# mini-v1_15-070.net
KiCad netlist of a schematic drawn in EAGLE
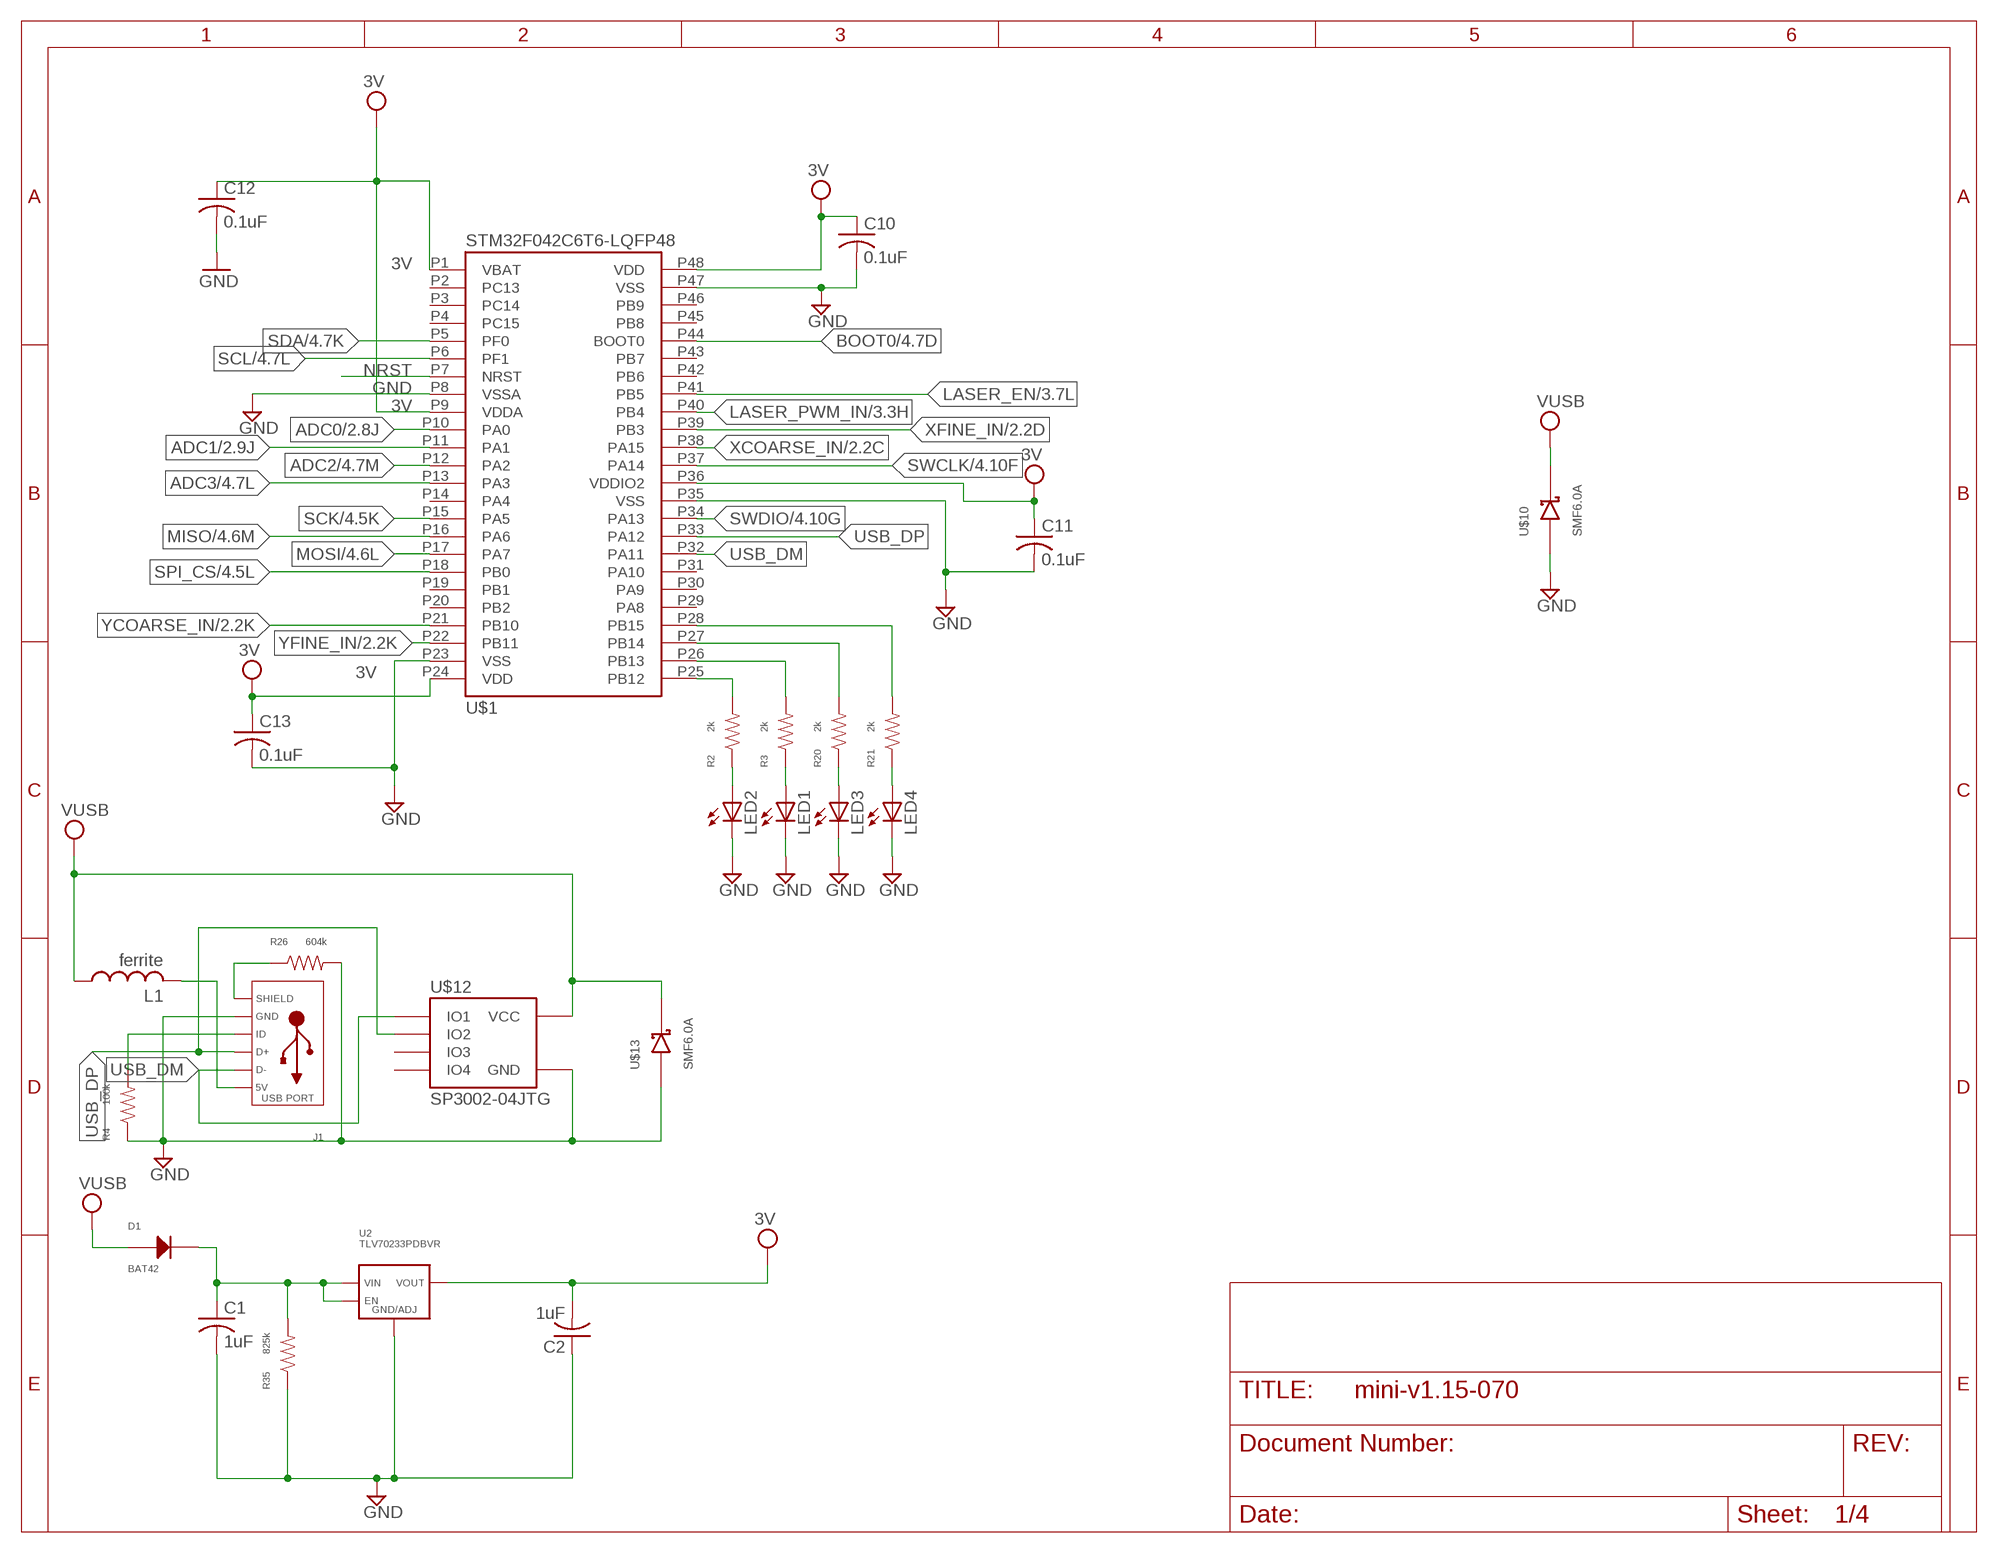
[diagram p0: schematic, sheet 1]
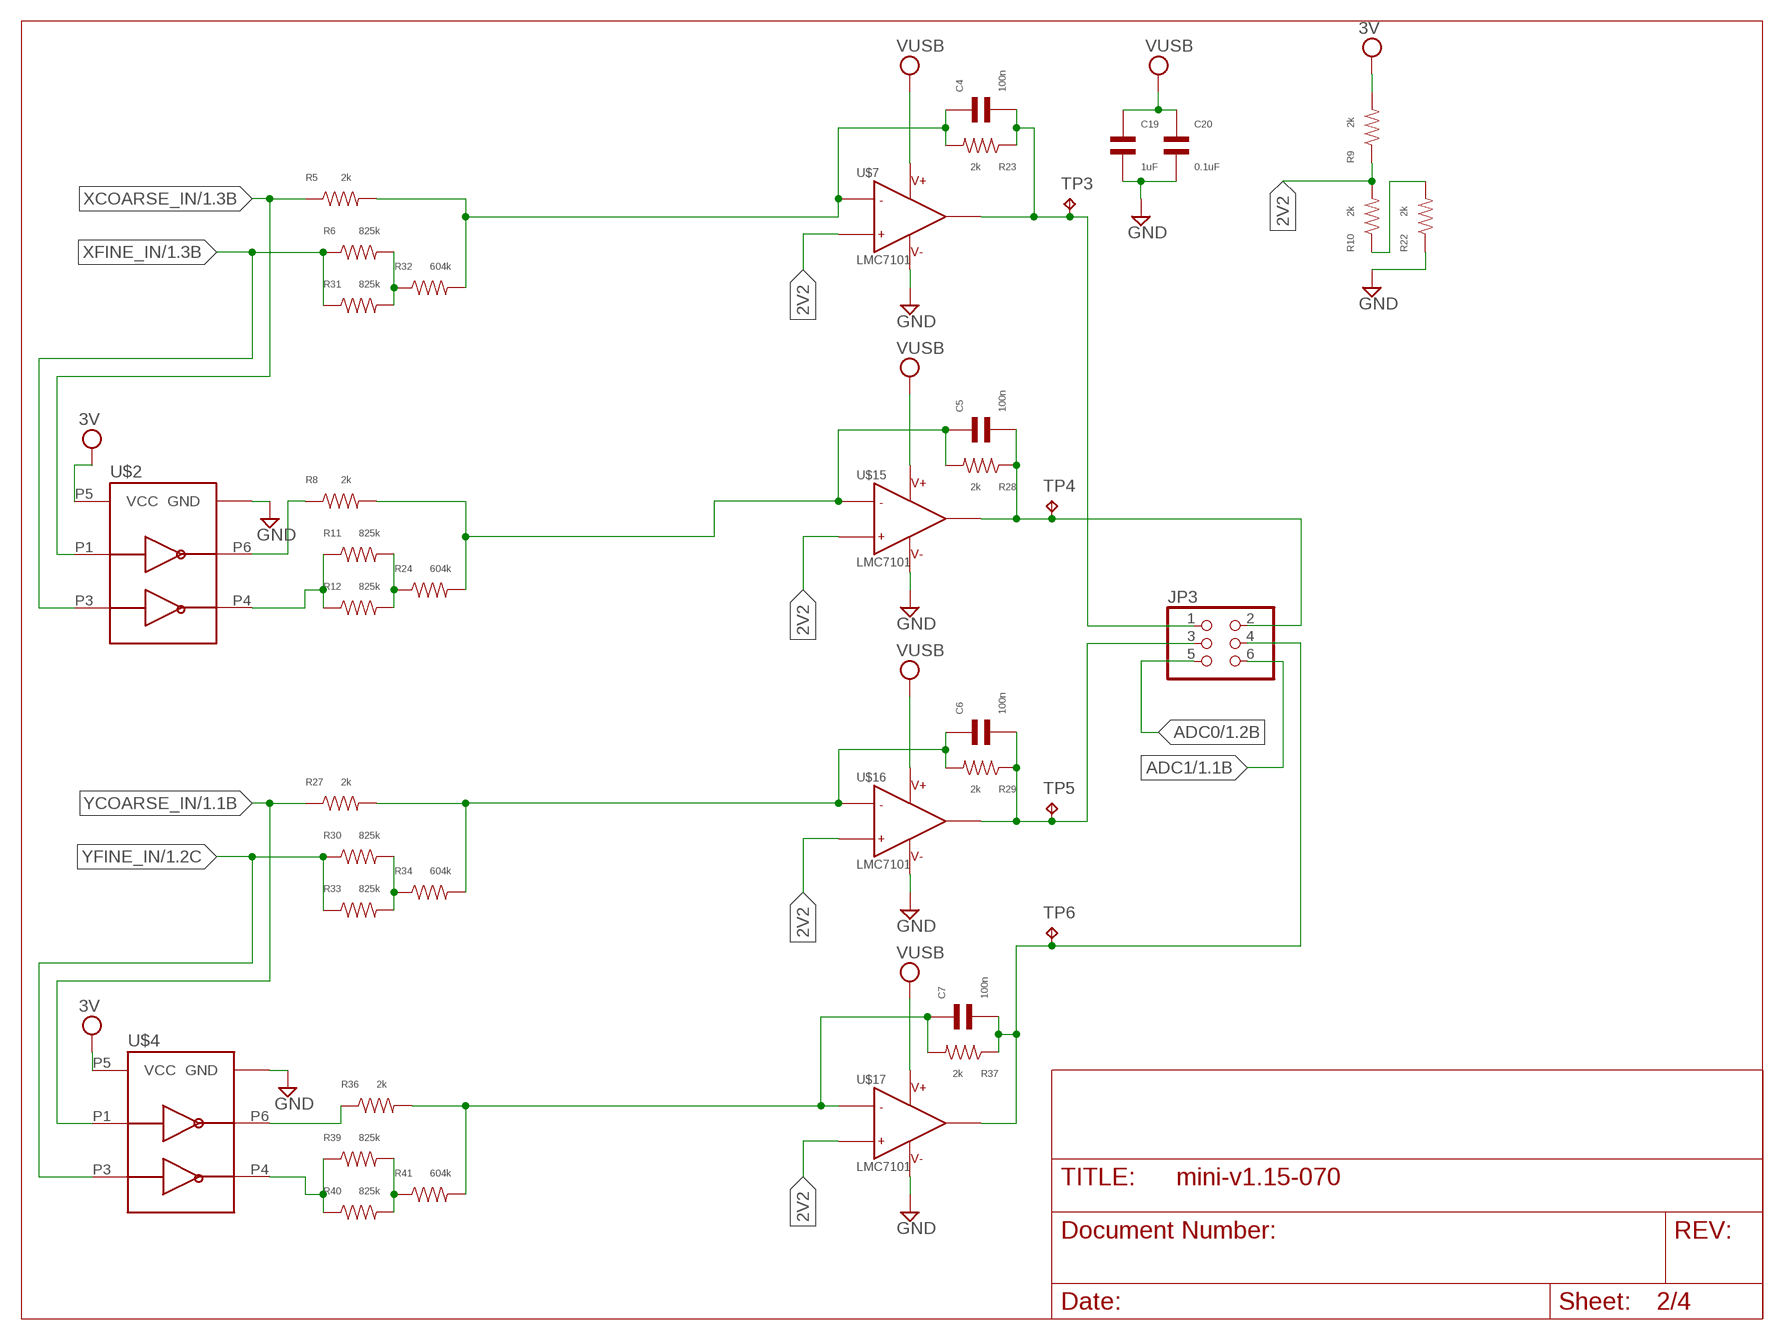
[diagram p1: schematic, sheet 2]
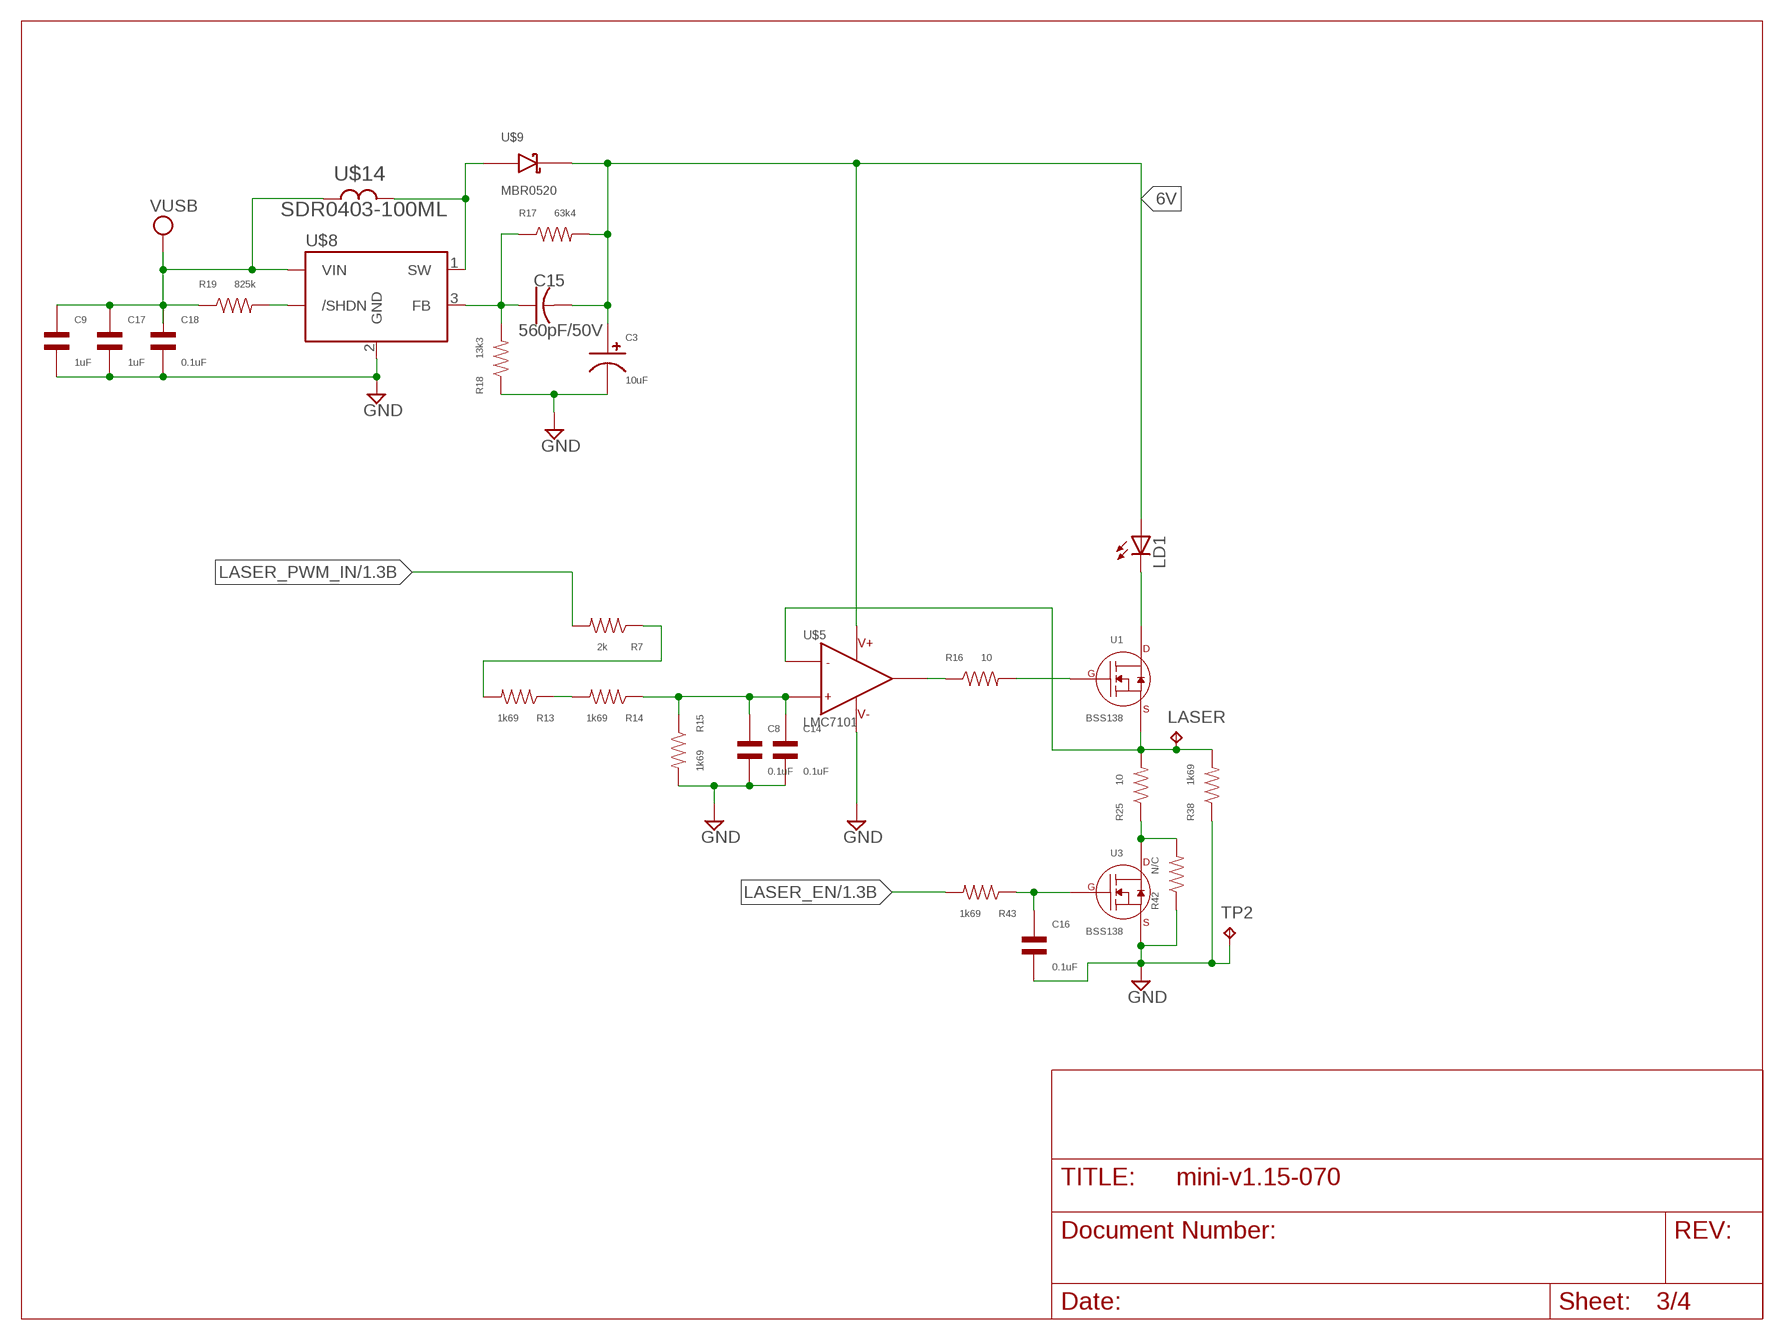
[diagram p2: schematic, sheet 3]
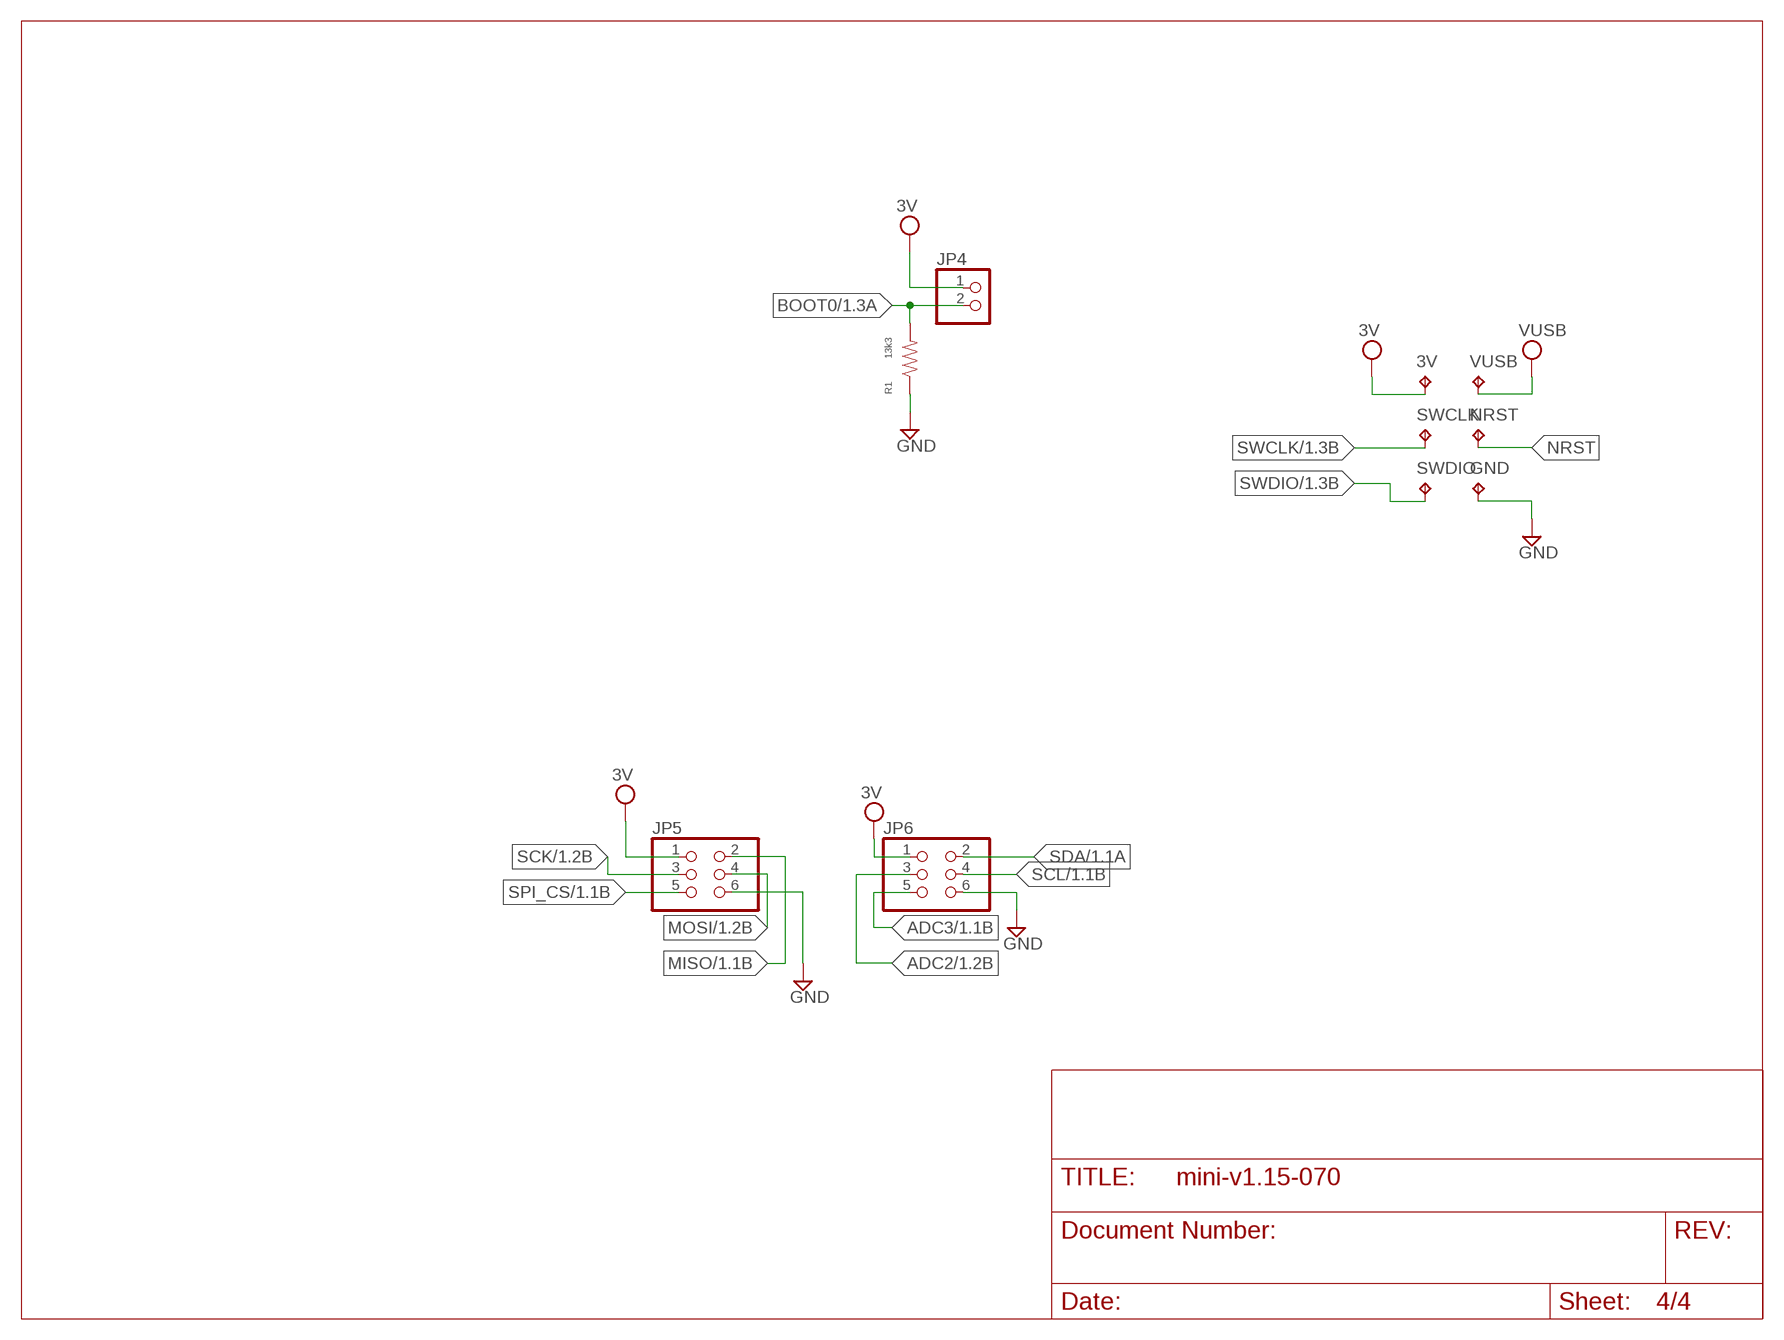
[diagram p3: schematic, sheet 4]

(export (version "E")
  (design (tool "Eeschema 10.0.6"))
  (components
    (comp (ref "C3")
      (value "10uF")
      (footprint "eagle-import:CP4MM")
      (libsource (lib "eagle-import") (part "CAPACITOR_P_4MM"))
    )
    (comp (ref "C8")
      (value "0.1uF")
      (footprint "eagle-import:C0603")
      (libsource (lib "eagle-import") (part "CAPACITOR_NP_0603"))
    )
    (comp (ref "C9")
      (value "1uF")
      (footprint "eagle-import:C0603")
      (libsource (lib "eagle-import") (part "CAPACITOR_NP_0603"))
    )
    (comp (ref "C14")
      (value "0.1uF")
      (footprint "eagle-import:C0603")
      (libsource (lib "eagle-import") (part "CAPACITOR_NP_0603"))
    )
    (comp (ref "C15")
      (value "560pF/50V")
      (footprint "eagle-import:C0603")
      (libsource (lib "eagle-import") (part "C-USC0603"))
    )
    (comp (ref "C16")
      (value "0.1uF")
      (footprint "eagle-import:C0603")
      (libsource (lib "eagle-import") (part "CAPACITOR_NP_0603"))
    )
    (comp (ref "C17")
      (value "1uF")
      (footprint "eagle-import:C0603")
      (libsource (lib "eagle-import") (part "CAPACITOR_NP_0603"))
    )
    (comp (ref "C18")
      (value "0.1uF")
      (footprint "eagle-import:C0603")
      (libsource (lib "eagle-import") (part "CAPACITOR_NP_0603"))
    )
    (comp (ref "LASER")
      (value "TPB2,54")
      (footprint "eagle-import:B2,54")
      (libsource (lib "eagle-import") (part "TPB2,54"))
    )
    (comp (ref "LD1")
      (value "SCOTT_LASERDIODELD3")
      (footprint "eagle-import:SCOTT_LASERDIODE3")
      (fields (field (name "MPN") "3 x (0552-2-15-15-11-27-10-0)"))
      (libsource (lib "eagle-import") (part "SCOTT_LASERDIODELD3"))
    )
    (comp (ref "R7")
      (value "2k")
      (footprint "eagle-import:R0603")
      (libsource (lib "eagle-import") (part "RESISTOR_0603"))
    )
    (comp (ref "R13")
      (value "1k69")
      (footprint "eagle-import:R0603")
      (libsource (lib "eagle-import") (part "RESISTOR_0603"))
    )
    (comp (ref "R14")
      (value "1k69")
      (footprint "eagle-import:R0603")
      (libsource (lib "eagle-import") (part "RESISTOR_0603"))
    )
    (comp (ref "R15")
      (value "1k69")
      (footprint "eagle-import:R0603")
      (libsource (lib "eagle-import") (part "RESISTOR_0603"))
    )
    (comp (ref "R16")
      (value "10")
      (footprint "eagle-import:R0603")
      (libsource (lib "eagle-import") (part "RESISTOR_0603"))
    )
    (comp (ref "R17")
      (value "63k4")
      (footprint "eagle-import:R0603")
      (libsource (lib "eagle-import") (part "RESISTOR_0603"))
    )
    (comp (ref "R18")
      (value "13k3")
      (footprint "eagle-import:R0603")
      (libsource (lib "eagle-import") (part "RESISTOR_0603"))
    )
    (comp (ref "R19")
      (value "825k")
      (footprint "eagle-import:R0603")
      (libsource (lib "eagle-import") (part "RESISTOR_0603"))
    )
    (comp (ref "R25")
      (value "10")
      (footprint "eagle-import:R0603")
      (libsource (lib "eagle-import") (part "RESISTOR_0603"))
    )
    (comp (ref "R38")
      (value "1k69")
      (footprint "eagle-import:R0603")
      (libsource (lib "eagle-import") (part "RESISTOR_0603"))
    )
    (comp (ref "R42")
      (value "N/C")
      (footprint "eagle-import:R0603")
      (libsource (lib "eagle-import") (part "RESISTOR_0603"))
    )
    (comp (ref "R43")
      (value "1k69")
      (footprint "eagle-import:R0603")
      (libsource (lib "eagle-import") (part "RESISTOR_0603"))
    )
    (comp (ref "TP2")
      (value "GND")
      (footprint "eagle-import:B2,54")
      (libsource (lib "eagle-import") (part "TPB2,54"))
    )
    (comp (ref "U$5")
      (value "LMC7101")
      (footprint "eagle-import:SOT23-5")
      (libsource (lib "eagle-import") (part "OPAMP-SINGLELMC7101"))
    )
    (comp (ref "U$8")
      (value "LMR62014")
      (footprint "eagle-import:SOT23-5")
      (libsource (lib "eagle-import") (part "LMR62014"))
    )
    (comp (ref "U$9")
      (value "MBR0520")
      (footprint "eagle-import:SOD123")
      (libsource (lib "eagle-import") (part "MBR0520"))
    )
    (comp (ref "U$14")
      (value "SDR0403-100ML")
      (footprint "eagle-import:SDR0403")
      (libsource (lib "eagle-import") (part "SDR0403"))
    )
    (comp (ref "U1")
      (value "BSS138")
      (footprint "eagle-import:SOT-23-3")
      (libsource (lib "eagle-import") (part "N-CHANNEL_FET_SOT-23-3"))
    )
    (comp (ref "U3")
      (value "BSS138")
      (footprint "eagle-import:SOT-23-3")
      (libsource (lib "eagle-import") (part "N-CHANNEL_FET_SOT-23-3"))
    )
    (comp (ref "C4")
      (value "100n")
      (footprint "eagle-import:C0603")
      (libsource (lib "eagle-import") (part "CAPACITOR_NP_0603"))
    )
    (comp (ref "C5")
      (value "100n")
      (footprint "eagle-import:C0603")
      (libsource (lib "eagle-import") (part "CAPACITOR_NP_0603"))
    )
    (comp (ref "C6")
      (value "100n")
      (footprint "eagle-import:C0603")
      (libsource (lib "eagle-import") (part "CAPACITOR_NP_0603"))
    )
    (comp (ref "C7")
      (value "100n")
      (footprint "eagle-import:C0603")
      (libsource (lib "eagle-import") (part "CAPACITOR_NP_0603"))
    )
    (comp (ref "C19")
      (value "1uF")
      (footprint "eagle-import:C0603")
      (libsource (lib "eagle-import") (part "CAPACITOR_NP_0603"))
    )
    (comp (ref "C20")
      (value "0.1uF")
      (footprint "eagle-import:C0603")
      (libsource (lib "eagle-import") (part "CAPACITOR_NP_0603"))
    )
    (comp (ref "JP3")
      (value "PINHD-2X3")
      (footprint "eagle-import:2X03")
      (libsource (lib "eagle-import") (part "PINHD-2X3"))
    )
    (comp (ref "R5")
      (value "2k")
      (footprint "eagle-import:R0603")
      (libsource (lib "eagle-import") (part "RESISTOR_0603"))
    )
    (comp (ref "R6")
      (value "825k")
      (footprint "eagle-import:R0603")
      (libsource (lib "eagle-import") (part "RESISTOR_0603"))
    )
    (comp (ref "R8")
      (value "2k")
      (footprint "eagle-import:R0603")
      (libsource (lib "eagle-import") (part "RESISTOR_0603"))
    )
    (comp (ref "R9")
      (value "2k")
      (footprint "eagle-import:R0603")
      (libsource (lib "eagle-import") (part "RESISTOR_0603"))
    )
    (comp (ref "R10")
      (value "2k")
      (footprint "eagle-import:R0603")
      (libsource (lib "eagle-import") (part "RESISTOR_0603"))
    )
    (comp (ref "R11")
      (value "825k")
      (footprint "eagle-import:R0603")
      (libsource (lib "eagle-import") (part "RESISTOR_0603"))
    )
    (comp (ref "R12")
      (value "825k")
      (footprint "eagle-import:R0603")
      (libsource (lib "eagle-import") (part "RESISTOR_0603"))
    )
    (comp (ref "R22")
      (value "2k")
      (footprint "eagle-import:R0603")
      (libsource (lib "eagle-import") (part "RESISTOR_0603"))
    )
    (comp (ref "R23")
      (value "2k")
      (footprint "eagle-import:R0603")
      (libsource (lib "eagle-import") (part "RESISTOR_0603"))
    )
    (comp (ref "R24")
      (value "604k")
      (footprint "eagle-import:R0603")
      (libsource (lib "eagle-import") (part "RESISTOR_0603"))
    )
    (comp (ref "R27")
      (value "2k")
      (footprint "eagle-import:R0603")
      (libsource (lib "eagle-import") (part "RESISTOR_0603"))
    )
    (comp (ref "R28")
      (value "2k")
      (footprint "eagle-import:R0603")
      (libsource (lib "eagle-import") (part "RESISTOR_0603"))
    )
    (comp (ref "R29")
      (value "2k")
      (footprint "eagle-import:R0603")
      (libsource (lib "eagle-import") (part "RESISTOR_0603"))
    )
    (comp (ref "R30")
      (value "825k")
      (footprint "eagle-import:R0603")
      (libsource (lib "eagle-import") (part "RESISTOR_0603"))
    )
    (comp (ref "R31")
      (value "825k")
      (footprint "eagle-import:R0603")
      (libsource (lib "eagle-import") (part "RESISTOR_0603"))
    )
    (comp (ref "R32")
      (value "604k")
      (footprint "eagle-import:R0603")
      (libsource (lib "eagle-import") (part "RESISTOR_0603"))
    )
    (comp (ref "R33")
      (value "825k")
      (footprint "eagle-import:R0603")
      (libsource (lib "eagle-import") (part "RESISTOR_0603"))
    )
    (comp (ref "R34")
      (value "604k")
      (footprint "eagle-import:R0603")
      (libsource (lib "eagle-import") (part "RESISTOR_0603"))
    )
    (comp (ref "R36")
      (value "2k")
      (footprint "eagle-import:R0603")
      (libsource (lib "eagle-import") (part "RESISTOR_0603"))
    )
    (comp (ref "R37")
      (value "2k")
      (footprint "eagle-import:R0603")
      (libsource (lib "eagle-import") (part "RESISTOR_0603"))
    )
    (comp (ref "R39")
      (value "825k")
      (footprint "eagle-import:R0603")
      (libsource (lib "eagle-import") (part "RESISTOR_0603"))
    )
    (comp (ref "R40")
      (value "825k")
      (footprint "eagle-import:R0603")
      (libsource (lib "eagle-import") (part "RESISTOR_0603"))
    )
    (comp (ref "R41")
      (value "604k")
      (footprint "eagle-import:R0603")
      (libsource (lib "eagle-import") (part "RESISTOR_0603"))
    )
    (comp (ref "TP3")
      (value "TPB1,27")
      (footprint "eagle-import:B1,27")
      (libsource (lib "eagle-import") (part "TPB1,27"))
    )
    (comp (ref "TP4")
      (value "TPB1,27")
      (footprint "eagle-import:B1,27")
      (libsource (lib "eagle-import") (part "TPB1,27"))
    )
    (comp (ref "TP5")
      (value "TPB1,27")
      (footprint "eagle-import:B1,27")
      (libsource (lib "eagle-import") (part "TPB1,27"))
    )
    (comp (ref "TP6")
      (value "TPB1,27")
      (footprint "eagle-import:B1,27")
      (libsource (lib "eagle-import") (part "TPB1,27"))
    )
    (comp (ref "U$2")
      (value "NC7WZ14P6X")
      (footprint "eagle-import:SC70-6")
      (libsource (lib "eagle-import") (part "NC7WZ14P6X"))
    )
    (comp (ref "U$4")
      (value "NC7WZ14P6X")
      (footprint "eagle-import:SC70-6")
      (libsource (lib "eagle-import") (part "NC7WZ14P6X"))
    )
    (comp (ref "U$7")
      (value "LMC7101")
      (footprint "eagle-import:SOT23-5")
      (libsource (lib "eagle-import") (part "LMC7101"))
    )
    (comp (ref "U$15")
      (value "LMC7101")
      (footprint "eagle-import:SOT23-5")
      (libsource (lib "eagle-import") (part "LMC7101"))
    )
    (comp (ref "U$16")
      (value "LMC7101")
      (footprint "eagle-import:SOT23-5")
      (libsource (lib "eagle-import") (part "LMC7101"))
    )
    (comp (ref "U$17")
      (value "LMC7101")
      (footprint "eagle-import:SOT23-5")
      (libsource (lib "eagle-import") (part "LMC7101"))
    )
    (comp (ref "3V")
      (value "TPB1,27")
      (footprint "eagle-import:B1,27")
      (libsource (lib "eagle-import") (part "TPB1,27"))
    )
    (comp (ref "GND")
      (value "TPB1,27")
      (footprint "eagle-import:B1,27")
      (libsource (lib "eagle-import") (part "TPB1,27"))
    )
    (comp (ref "JP4")
      (value "PINHD-1X2")
      (footprint "eagle-import:1X02")
      (libsource (lib "eagle-import") (part "PINHD-1X2"))
    )
    (comp (ref "JP5")
      (value "PINHD-2X3")
      (footprint "eagle-import:2X03")
      (libsource (lib "eagle-import") (part "PINHD-2X3"))
    )
    (comp (ref "JP6")
      (value "PINHD-2X3")
      (footprint "eagle-import:2X03")
      (libsource (lib "eagle-import") (part "PINHD-2X3"))
    )
    (comp (ref "NRST")
      (value "TPB1,27")
      (footprint "eagle-import:B1,27")
      (libsource (lib "eagle-import") (part "TPB1,27"))
    )
    (comp (ref "R1")
      (value "13k3")
      (footprint "eagle-import:R0603")
      (libsource (lib "eagle-import") (part "RESISTOR_0603"))
    )
    (comp (ref "SWCLK")
      (value "TPB1,27")
      (footprint "eagle-import:B1,27")
      (libsource (lib "eagle-import") (part "TPB1,27"))
    )
    (comp (ref "SWDIO")
      (value "TPB1,27")
      (footprint "eagle-import:B1,27")
      (libsource (lib "eagle-import") (part "TPB1,27"))
    )
    (comp (ref "VUSB")
      (value "TPB1,27")
      (footprint "eagle-import:B1,27")
      (libsource (lib "eagle-import") (part "TPB1,27"))
    )
    (comp (ref "C1")
      (value "1uF")
      (footprint "eagle-import:C0603")
      (libsource (lib "eagle-import") (part "C-USC0603"))
    )
    (comp (ref "C2")
      (value "1uF")
      (footprint "eagle-import:C0603")
      (libsource (lib "eagle-import") (part "C-USC0603"))
    )
    (comp (ref "C10")
      (value "0.1uF")
      (footprint "eagle-import:C0603")
      (libsource (lib "eagle-import") (part "C-USC0603"))
    )
    (comp (ref "C11")
      (value "0.1uF")
      (footprint "eagle-import:C0603")
      (libsource (lib "eagle-import") (part "C-USC0603"))
    )
    (comp (ref "C12")
      (value "0.1uF")
      (footprint "eagle-import:C0603")
      (libsource (lib "eagle-import") (part "C-USC0603"))
    )
    (comp (ref "C13")
      (value "0.1uF")
      (footprint "eagle-import:C0603")
      (libsource (lib "eagle-import") (part "C-USC0603"))
    )
    (comp (ref "D1")
      (value "BAT42")
      (footprint "eagle-import:SOD-123")
      (libsource (lib "eagle-import") (part "DIODE_SOD-123"))
    )
    (comp (ref "J1")
      (value "USB_MICRO_RIGHT")
      (footprint "eagle-import:MICROUSB-RIGHT")
      (libsource (lib "eagle-import") (part "USB_MICRO_RIGHT"))
    )
    (comp (ref "L1")
      (value "ferrite")
      (footprint "eagle-import:C0603")
      (libsource (lib "eagle-import") (part "L-US"))
    )
    (comp (ref "LED1")
      (value "LEDCHIP-LED0603")
      (footprint "eagle-import:CHIP-LED0603")
      (libsource (lib "eagle-import") (part "LEDCHIP-LED0603"))
    )
    (comp (ref "LED2")
      (value "LEDCHIP-LED0603")
      (footprint "eagle-import:CHIP-LED0603")
      (libsource (lib "eagle-import") (part "LEDCHIP-LED0603"))
    )
    (comp (ref "LED3")
      (value "LEDCHIP-LED0603")
      (footprint "eagle-import:CHIP-LED0603")
      (libsource (lib "eagle-import") (part "LEDCHIP-LED0603"))
    )
    (comp (ref "LED4")
      (value "LEDCHIP-LED0603")
      (footprint "eagle-import:CHIP-LED0603")
      (libsource (lib "eagle-import") (part "LEDCHIP-LED0603"))
    )
    (comp (ref "R2")
      (value "2k")
      (footprint "eagle-import:R0603")
      (libsource (lib "eagle-import") (part "RESISTOR_0603"))
    )
    (comp (ref "R3")
      (value "2k")
      (footprint "eagle-import:R0603")
      (libsource (lib "eagle-import") (part "RESISTOR_0603"))
    )
    (comp (ref "R4")
      (value "100k")
      (footprint "eagle-import:R0603")
      (libsource (lib "eagle-import") (part "RESISTOR_0603"))
    )
    (comp (ref "R20")
      (value "2k")
      (footprint "eagle-import:R0603")
      (libsource (lib "eagle-import") (part "RESISTOR_0603"))
    )
    (comp (ref "R21")
      (value "2k")
      (footprint "eagle-import:R0603")
      (libsource (lib "eagle-import") (part "RESISTOR_0603"))
    )
    (comp (ref "R26")
      (value "604k")
      (footprint "eagle-import:R0603")
      (libsource (lib "eagle-import") (part "RESISTOR_0603"))
    )
    (comp (ref "R35")
      (value "825k")
      (footprint "eagle-import:R0603")
      (libsource (lib "eagle-import") (part "RESISTOR_0603"))
    )
    (comp (ref "U$1")
      (value "STM32F042C6T6-LQFP48")
      (footprint "eagle-import:LQFP48")
      (libsource (lib "eagle-import") (part "STM32F042-LQFP48"))
    )
    (comp (ref "U$10")
      (value "SMF6.0A")
      (footprint "eagle-import:SOD123")
      (libsource (lib "eagle-import") (part "MBR0520"))
    )
    (comp (ref "U$12")
      (value "SP3002-04JTG")
      (footprint "eagle-import:SC70-6")
      (libsource (lib "eagle-import") (part "SP3002"))
    )
    (comp (ref "U$13")
      (value "SMF6.0A")
      (footprint "eagle-import:SOD123")
      (libsource (lib "eagle-import") (part "MBR0520"))
    )
    (comp (ref "U2")
      (value "TLV70233PDBVR")
      (footprint "eagle-import:SOT-23-5")
      (libsource (lib "eagle-import") (part "TLV70233PDBVR"))
    )
  )
  (nets
    (net (code "1") (name "2V2") (class "Default")
      (node (ref "R10") (pin "P$2") (pinfunction "P$2_P$2") (pintype "passive"))
      (node (ref "R9") (pin "P$1") (pinfunction "P$1_P$1") (pintype "passive"))
      (node (ref "U$15") (pin "3") (pinfunction "P3_3") (pintype "bidirectional"))
      (node (ref "U$16") (pin "3") (pinfunction "P3_3") (pintype "bidirectional"))
      (node (ref "U$17") (pin "3") (pinfunction "P3_3") (pintype "bidirectional"))
      (node (ref "U$7") (pin "3") (pinfunction "P3_3") (pintype "bidirectional"))
    )
    (net (code "2") (name "3V") (class "Default")
      (node (ref "3V") (pin "TP") (pinfunction "TP_TP") (pintype "input"))
      (node (ref "C10") (pin "1") (pinfunction "1_1") (pintype "passive"))
      (node (ref "C11") (pin "1") (pinfunction "1_1") (pintype "passive"))
      (node (ref "C12") (pin "1") (pinfunction "1_1") (pintype "passive"))
      (node (ref "C13") (pin "1") (pinfunction "1_1") (pintype "passive"))
      (node (ref "C2") (pin "2") (pinfunction "2_2") (pintype "passive"))
      (node (ref "JP4") (pin "1") (pinfunction "1_1") (pintype "passive"))
      (node (ref "JP5") (pin "1") (pinfunction "1_1") (pintype "passive"))
      (node (ref "JP6") (pin "1") (pinfunction "1_1") (pintype "passive"))
      (node (ref "R9") (pin "P$2") (pinfunction "P$2_P$2") (pintype "passive"))
      (node (ref "U$1") (pin "P1") (pinfunction "VBAT_P1") (pintype "bidirectional"))
      (node (ref "U$1") (pin "P24") (pinfunction "VDD_P24") (pintype "bidirectional"))
      (node (ref "U$1") (pin "P36") (pinfunction "VDDIO2_P36") (pintype "bidirectional"))
      (node (ref "U$1") (pin "P48") (pinfunction "VDD_P48") (pintype "bidirectional"))
      (node (ref "U$1") (pin "P9") (pinfunction "VDDA_P9") (pintype "bidirectional"))
      (node (ref "U$2") (pin "P5") (pinfunction "VCC_P5") (pintype "power_in"))
      (node (ref "U$4") (pin "P5") (pinfunction "VCC_P5") (pintype "power_in"))
      (node (ref "U2") (pin "P$5") (pinfunction "VOUT_P$5") (pintype "bidirectional"))
    )
    (net (code "3") (name "6V") (class "Default")
      (node (ref "C15") (pin "2") (pinfunction "2_2") (pintype "passive"))
      (node (ref "C3") (pin "P$1") (pinfunction "P$1_P$1") (pintype "passive"))
      (node (ref "LD1") (pin "P$1") (pinfunction "A_P$1") (pintype "passive"))
      (node (ref "R17") (pin "P$2") (pinfunction "P$2_P$2") (pintype "passive"))
      (node (ref "U$5") (pin "2") (pinfunction "V+_2") (pintype "power_in"))
      (node (ref "U$9") (pin "CATHODE") (pinfunction "CATHODE_CATHODE") (pintype "bidirectional"))
    )
    (net (code "4") (name "ADC0") (class "Default")
      (node (ref "JP3") (pin "5") (pinfunction "5_5") (pintype "passive"))
      (node (ref "U$1") (pin "P10") (pinfunction "PA0_P10") (pintype "bidirectional"))
    )
    (net (code "5") (name "ADC1") (class "Default")
      (node (ref "JP3") (pin "6") (pinfunction "6_6") (pintype "passive"))
      (node (ref "U$1") (pin "P11") (pinfunction "PA1_P11") (pintype "bidirectional"))
    )
    (net (code "6") (name "ADC2") (class "Default")
      (node (ref "JP6") (pin "3") (pinfunction "3_3") (pintype "passive"))
      (node (ref "U$1") (pin "P12") (pinfunction "PA2_P12") (pintype "bidirectional"))
    )
    (net (code "7") (name "ADC3") (class "Default")
      (node (ref "JP6") (pin "5") (pinfunction "5_5") (pintype "passive"))
      (node (ref "U$1") (pin "P13") (pinfunction "PA3_P13") (pintype "bidirectional"))
    )
    (net (code "8") (name "BOOT0") (class "Default")
      (node (ref "JP4") (pin "2") (pinfunction "2_2") (pintype "passive"))
      (node (ref "R1") (pin "P$2") (pinfunction "P$2_P$2") (pintype "passive"))
      (node (ref "U$1") (pin "P44") (pinfunction "BOOT0_P44") (pintype "bidirectional"))
    )
    (net (code "9") (name "GND") (class "Default")
      (node (ref "C1") (pin "2") (pinfunction "2_2") (pintype "passive"))
      (node (ref "C10") (pin "2") (pinfunction "2_2") (pintype "passive"))
      (node (ref "C11") (pin "2") (pinfunction "2_2") (pintype "passive"))
      (node (ref "C12") (pin "2") (pinfunction "2_2") (pintype "passive"))
      (node (ref "C13") (pin "2") (pinfunction "2_2") (pintype "passive"))
      (node (ref "C14") (pin "P$2") (pinfunction "P$2_P$2") (pintype "passive"))
      (node (ref "C16") (pin "P$2") (pinfunction "P$2_P$2") (pintype "passive"))
      (node (ref "C17") (pin "P$2") (pinfunction "P$2_P$2") (pintype "passive"))
      (node (ref "C18") (pin "P$2") (pinfunction "P$2_P$2") (pintype "passive"))
      (node (ref "C19") (pin "P$2") (pinfunction "P$2_P$2") (pintype "passive"))
      (node (ref "C2") (pin "1") (pinfunction "1_1") (pintype "passive"))
      (node (ref "C20") (pin "P$2") (pinfunction "P$2_P$2") (pintype "passive"))
      (node (ref "C3") (pin "P$2") (pinfunction "P$2_P$2") (pintype "passive"))
      (node (ref "C8") (pin "P$2") (pinfunction "P$2_P$2") (pintype "passive"))
      (node (ref "C9") (pin "P$2") (pinfunction "P$2_P$2") (pintype "passive"))
      (node (ref "GND") (pin "TP") (pinfunction "TP_TP") (pintype "input"))
      (node (ref "J1") (pin "5") (pinfunction "GND_5") (pintype "power_in"))
      (node (ref "JP5") (pin "6") (pinfunction "6_6") (pintype "passive"))
      (node (ref "JP6") (pin "6") (pinfunction "6_6") (pintype "passive"))
      (node (ref "LED1") (pin "C") (pinfunction "C_C") (pintype "passive"))
      (node (ref "LED2") (pin "C") (pinfunction "C_C") (pintype "passive"))
      (node (ref "LED3") (pin "C") (pinfunction "C_C") (pintype "passive"))
      (node (ref "LED4") (pin "C") (pinfunction "C_C") (pintype "passive"))
      (node (ref "R1") (pin "P$1") (pinfunction "P$1_P$1") (pintype "passive"))
      (node (ref "R15") (pin "P$2") (pinfunction "P$2_P$2") (pintype "passive"))
      (node (ref "R18") (pin "P$1") (pinfunction "P$1_P$1") (pintype "passive"))
      (node (ref "R22") (pin "P$1") (pinfunction "P$1_P$1") (pintype "passive"))
      (node (ref "R26") (pin "P$2") (pinfunction "P$2_P$2") (pintype "passive"))
      (node (ref "R35") (pin "P$1") (pinfunction "P$1_P$1") (pintype "passive"))
      (node (ref "R38") (pin "P$1") (pinfunction "P$1_P$1") (pintype "passive"))
      (node (ref "R4") (pin "P$1") (pinfunction "P$1_P$1") (pintype "passive"))
      (node (ref "R42") (pin "P$1") (pinfunction "P$1_P$1") (pintype "passive"))
      (node (ref "TP2") (pin "TP") (pinfunction "TP_TP") (pintype "input"))
      (node (ref "U$1") (pin "P23") (pinfunction "VSS_P23") (pintype "bidirectional"))
      (node (ref "U$1") (pin "P35") (pinfunction "VSS_P35") (pintype "bidirectional"))
      (node (ref "U$1") (pin "P47") (pinfunction "VSS_P47") (pintype "bidirectional"))
      (node (ref "U$1") (pin "P8") (pinfunction "VSSA_P8") (pintype "bidirectional"))
      (node (ref "U$10") (pin "ANODE") (pinfunction "ANODE_ANODE") (pintype "bidirectional"))
      (node (ref "U$12") (pin "P2") (pinfunction "GND_P2") (pintype "power_in"))
      (node (ref "U$13") (pin "ANODE") (pinfunction "ANODE_ANODE") (pintype "bidirectional"))
      (node (ref "U$15") (pin "5") (pinfunction "P5_5") (pintype "power_in"))
      (node (ref "U$16") (pin "5") (pinfunction "P5_5") (pintype "power_in"))
      (node (ref "U$17") (pin "5") (pinfunction "P5_5") (pintype "power_in"))
      (node (ref "U$2") (pin "P2") (pinfunction "GND_P2") (pintype "power_in"))
      (node (ref "U$4") (pin "P2") (pinfunction "GND_P2") (pintype "power_in"))
      (node (ref "U$5") (pin "5") (pinfunction "V-_5") (pintype "power_in"))
      (node (ref "U$7") (pin "5") (pinfunction "P5_5") (pintype "power_in"))
      (node (ref "U$8") (pin "2") (pinfunction "GND_2") (pintype "bidirectional"))
      (node (ref "U2") (pin "P$2") (pinfunction "GND/ADJ_P$2") (pintype "bidirectional"))
      (node (ref "U3") (pin "P$2") (pinfunction "SOURCE_P$2") (pintype "bidirectional"))
    )
    (net (code "10") (name "LASER_EN") (class "Default")
      (node (ref "R43") (pin "P$2") (pinfunction "P$2_P$2") (pintype "passive"))
      (node (ref "U$1") (pin "P41") (pinfunction "PB5_P41") (pintype "bidirectional"))
    )
    (net (code "11") (name "LASER_PWM_IN") (class "Default")
      (node (ref "R7") (pin "P$2") (pinfunction "P$2_P$2") (pintype "passive"))
      (node (ref "U$1") (pin "P40") (pinfunction "PB4_P40") (pintype "bidirectional"))
    )
    (net (code "12") (name "MISO") (class "Default")
      (node (ref "JP5") (pin "2") (pinfunction "2_2") (pintype "passive"))
      (node (ref "U$1") (pin "P16") (pinfunction "PA6_P16") (pintype "bidirectional"))
    )
    (net (code "13") (name "MOSI") (class "Default")
      (node (ref "JP5") (pin "4") (pinfunction "4_4") (pintype "passive"))
      (node (ref "U$1") (pin "P17") (pinfunction "PA7_P17") (pintype "bidirectional"))
    )
    (net (code "14") (name "NRST") (class "Default")
      (node (ref "NRST") (pin "TP") (pinfunction "TP_TP") (pintype "input"))
      (node (ref "U$1") (pin "P7") (pinfunction "NRST_P7") (pintype "bidirectional"))
    )
    (net (code "15") (name "Net-(J1-5V)") (class "Default")
      (node (ref "J1") (pin "1") (pinfunction "5V_1") (pintype "power_in"))
      (node (ref "L1") (pin "2") (pinfunction "2_2") (pintype "passive"))
    )
    (net (code "16") (name "Net-(J1-ID)") (class "Default")
      (node (ref "J1") (pin "4") (pinfunction "ID_4") (pintype "bidirectional"))
      (node (ref "R4") (pin "P$2") (pinfunction "P$2_P$2") (pintype "passive"))
    )
    (net (code "17") (name "Net-(J1-SLD-PadS1)") (class "Default")
      (node (ref "J1") (pin "S1") (pinfunction "SLD_S1") (pintype "power_in"))
      (node (ref "J1") (pin "S2") (pinfunction "SLD_S2") (pintype "power_in"))
      (node (ref "J1") (pin "S3") (pinfunction "SLD_S3") (pintype "power_in"))
      (node (ref "J1") (pin "S4") (pinfunction "SLD_S4") (pintype "power_in"))
      (node (ref "J1") (pin "S5") (pinfunction "SLD_S5") (pintype "power_in"))
      (node (ref "J1") (pin "S6") (pinfunction "SLD_S6") (pintype "power_in"))
      (node (ref "R26") (pin "P$1") (pinfunction "P$1_P$1") (pintype "passive"))
    )
    (net (code "18") (name "Net-(LD1-C)") (class "Default")
      (node (ref "LD1") (pin "P$3") (pinfunction "C_P$3") (pintype "passive"))
      (node (ref "U1") (pin "P$3") (pinfunction "DRAIN_P$3") (pintype "bidirectional"))
    )
    (net (code "19") (name "Net-(LED1-PadA)") (class "Default")
      (node (ref "LED1") (pin "A") (pinfunction "A_A") (pintype "passive"))
      (node (ref "R3") (pin "P$1") (pinfunction "P$1_P$1") (pintype "passive"))
    )
    (net (code "20") (name "Net-(LED2-PadA)") (class "Default")
      (node (ref "LED2") (pin "A") (pinfunction "A_A") (pintype "passive"))
      (node (ref "R2") (pin "P$1") (pinfunction "P$1_P$1") (pintype "passive"))
    )
    (net (code "21") (name "Net-(LED3-PadA)") (class "Default")
      (node (ref "LED3") (pin "A") (pinfunction "A_A") (pintype "passive"))
      (node (ref "R20") (pin "P$1") (pinfunction "P$1_P$1") (pintype "passive"))
    )
    (net (code "22") (name "Net-(LED4-PadA)") (class "Default")
      (node (ref "LED4") (pin "A") (pinfunction "A_A") (pintype "passive"))
      (node (ref "R21") (pin "P$1") (pinfunction "P$1_P$1") (pintype "passive"))
    )
    (net (code "23") (name "Net-(R10-PadP$1)") (class "Default")
      (node (ref "R10") (pin "P$1") (pinfunction "P$1_P$1") (pintype "passive"))
      (node (ref "R22") (pin "P$2") (pinfunction "P$2_P$2") (pintype "passive"))
    )
    (net (code "24") (name "Net-(R11-PadP$2)") (class "Default")
      (node (ref "R11") (pin "P$2") (pinfunction "P$2_P$2") (pintype "passive"))
      (node (ref "R12") (pin "P$2") (pinfunction "P$2_P$2") (pintype "passive"))
      (node (ref "R24") (pin "P$1") (pinfunction "P$1_P$1") (pintype "passive"))
    )
    (net (code "25") (name "Net-(R13-PadP$1)") (class "Default")
      (node (ref "R13") (pin "P$1") (pinfunction "P$1_P$1") (pintype "passive"))
      (node (ref "R14") (pin "P$2") (pinfunction "P$2_P$2") (pintype "passive"))
    )
    (net (code "26") (name "Net-(R13-PadP$2)") (class "Default")
      (node (ref "R13") (pin "P$2") (pinfunction "P$2_P$2") (pintype "passive"))
      (node (ref "R7") (pin "P$1") (pinfunction "P$1_P$1") (pintype "passive"))
    )
    (net (code "27") (name "Net-(R30-PadP$2)") (class "Default")
      (node (ref "R30") (pin "P$2") (pinfunction "P$2_P$2") (pintype "passive"))
      (node (ref "R33") (pin "P$2") (pinfunction "P$2_P$2") (pintype "passive"))
      (node (ref "R34") (pin "P$1") (pinfunction "P$1_P$1") (pintype "passive"))
    )
    (net (code "28") (name "Net-(R31-PadP$2)") (class "Default")
      (node (ref "R31") (pin "P$2") (pinfunction "P$2_P$2") (pintype "passive"))
      (node (ref "R32") (pin "P$1") (pinfunction "P$1_P$1") (pintype "passive"))
      (node (ref "R6") (pin "P$2") (pinfunction "P$2_P$2") (pintype "passive"))
    )
    (net (code "29") (name "Net-(R39-PadP$2)") (class "Default")
      (node (ref "R39") (pin "P$2") (pinfunction "P$2_P$2") (pintype "passive"))
      (node (ref "R40") (pin "P$2") (pinfunction "P$2_P$2") (pintype "passive"))
      (node (ref "R41") (pin "P$1") (pinfunction "P$1_P$1") (pintype "passive"))
    )
    (net (code "30") (name "Net-(U$1-PB12)") (class "Default")
      (node (ref "R2") (pin "P$2") (pinfunction "P$2_P$2") (pintype "passive"))
      (node (ref "U$1") (pin "P25") (pinfunction "PB12_P25") (pintype "bidirectional"))
    )
    (net (code "31") (name "Net-(U$1-PB13)") (class "Default")
      (node (ref "R3") (pin "P$2") (pinfunction "P$2_P$2") (pintype "passive"))
      (node (ref "U$1") (pin "P26") (pinfunction "PB13_P26") (pintype "bidirectional"))
    )
    (net (code "32") (name "Net-(U$1-PB14)") (class "Default")
      (node (ref "R20") (pin "P$2") (pinfunction "P$2_P$2") (pintype "passive"))
      (node (ref "U$1") (pin "P27") (pinfunction "PB14_P27") (pintype "bidirectional"))
    )
    (net (code "33") (name "Net-(U$1-PB15)") (class "Default")
      (node (ref "R21") (pin "P$2") (pinfunction "P$2_P$2") (pintype "passive"))
      (node (ref "U$1") (pin "P28") (pinfunction "PB15_P28") (pintype "bidirectional"))
    )
    (net (code "34") (name "Net-(U$2-Y1)") (class "Default")
      (node (ref "R8") (pin "P$1") (pinfunction "P$1_P$1") (pintype "passive"))
      (node (ref "U$2") (pin "P6") (pinfunction "Y1_P6") (pintype "output"))
    )
    (net (code "35") (name "Net-(U$2-Y2)") (class "Default")
      (node (ref "R11") (pin "P$1") (pinfunction "P$1_P$1") (pintype "passive"))
      (node (ref "R12") (pin "P$1") (pinfunction "P$1_P$1") (pintype "passive"))
      (node (ref "U$2") (pin "P4") (pinfunction "Y2_P4") (pintype "output"))
    )
    (net (code "36") (name "Net-(U$4-Y1)") (class "Default")
      (node (ref "R36") (pin "P$1") (pinfunction "P$1_P$1") (pintype "passive"))
      (node (ref "U$4") (pin "P6") (pinfunction "Y1_P6") (pintype "output"))
    )
    (net (code "37") (name "Net-(U$4-Y2)") (class "Default")
      (node (ref "R39") (pin "P$1") (pinfunction "P$1_P$1") (pintype "passive"))
      (node (ref "R40") (pin "P$1") (pinfunction "P$1_P$1") (pintype "passive"))
      (node (ref "U$4") (pin "P4") (pinfunction "Y2_P4") (pintype "output"))
    )
    (net (code "38") (name "Net-(U$5-IN+)") (class "Default")
      (node (ref "C14") (pin "P$1") (pinfunction "P$1_P$1") (pintype "passive"))
      (node (ref "C8") (pin "P$1") (pinfunction "P$1_P$1") (pintype "passive"))
      (node (ref "R14") (pin "P$1") (pinfunction "P$1_P$1") (pintype "passive"))
      (node (ref "R15") (pin "P$1") (pinfunction "P$1_P$1") (pintype "passive"))
      (node (ref "U$5") (pin "3") (pinfunction "IN+_3") (pintype "bidirectional"))
    )
    (net (code "39") (name "Net-(U$5-IN-)") (class "Default")
      (node (ref "LASER") (pin "TP") (pinfunction "TP_TP") (pintype "input"))
      (node (ref "R25") (pin "P$2") (pinfunction "P$2_P$2") (pintype "passive"))
      (node (ref "R38") (pin "P$2") (pinfunction "P$2_P$2") (pintype "passive"))
      (node (ref "U$5") (pin "4") (pinfunction "IN-_4") (pintype "bidirectional"))
      (node (ref "U1") (pin "P$2") (pinfunction "SOURCE_P$2") (pintype "bidirectional"))
    )
    (net (code "40") (name "Net-(U$5-OUT)") (class "Default")
      (node (ref "R16") (pin "P$1") (pinfunction "P$1_P$1") (pintype "passive"))
      (node (ref "U$5") (pin "1") (pinfunction "OUT_1") (pintype "bidirectional"))
    )
    (net (code "41") (name "Net-(U$7-P1)") (class "Default")
      (node (ref "C4") (pin "P$2") (pinfunction "P$2_P$2") (pintype "passive"))
      (node (ref "JP3") (pin "1") (pinfunction "1_1") (pintype "passive"))
      (node (ref "R23") (pin "P$1") (pinfunction "P$1_P$1") (pintype "passive"))
      (node (ref "TP3") (pin "TP") (pinfunction "TP_TP") (pintype "input"))
      (node (ref "U$7") (pin "1") (pinfunction "P1_1") (pintype "bidirectional"))
    )
    (net (code "42") (name "Net-(U$7-P4)") (class "Default")
      (node (ref "C4") (pin "P$1") (pinfunction "P$1_P$1") (pintype "passive"))
      (node (ref "R23") (pin "P$2") (pinfunction "P$2_P$2") (pintype "passive"))
      (node (ref "R32") (pin "P$2") (pinfunction "P$2_P$2") (pintype "passive"))
      (node (ref "R5") (pin "P$2") (pinfunction "P$2_P$2") (pintype "passive"))
      (node (ref "U$7") (pin "4") (pinfunction "P4_4") (pintype "bidirectional"))
    )
    (net (code "43") (name "Net-(U$8-FB)") (class "Default")
      (node (ref "C15") (pin "1") (pinfunction "1_1") (pintype "passive"))
      (node (ref "R17") (pin "P$1") (pinfunction "P$1_P$1") (pintype "passive"))
      (node (ref "R18") (pin "P$2") (pinfunction "P$2_P$2") (pintype "passive"))
      (node (ref "U$8") (pin "3") (pinfunction "FB_3") (pintype "bidirectional"))
    )
    (net (code "44") (name "Net-(U$8-SW)") (class "Default")
      (node (ref "U$14") (pin "P$2") (pinfunction "P$2_P$2") (pintype "bidirectional"))
      (node (ref "U$8") (pin "1") (pinfunction "SW_1") (pintype "bidirectional"))
      (node (ref "U$9") (pin "ANODE") (pinfunction "ANODE_ANODE") (pintype "bidirectional"))
    )
    (net (code "45") (name "Net-(U$8-{slash}SHDN)") (class "Default")
      (node (ref "R19") (pin "P$2") (pinfunction "P$2_P$2") (pintype "passive"))
      (node (ref "U$8") (pin "4") (pinfunction "/SHDN_4") (pintype "bidirectional"))
    )
    (net (code "46") (name "Net-(U$15-P1)") (class "Default")
      (node (ref "C5") (pin "P$2") (pinfunction "P$2_P$2") (pintype "passive"))
      (node (ref "JP3") (pin "2") (pinfunction "2_2") (pintype "passive"))
      (node (ref "R28") (pin "P$1") (pinfunction "P$1_P$1") (pintype "passive"))
      (node (ref "TP4") (pin "TP") (pinfunction "TP_TP") (pintype "input"))
      (node (ref "U$15") (pin "1") (pinfunction "P1_1") (pintype "bidirectional"))
    )
    (net (code "47") (name "Net-(U$15-P4)") (class "Default")
      (node (ref "C5") (pin "P$1") (pinfunction "P$1_P$1") (pintype "passive"))
      (node (ref "R24") (pin "P$2") (pinfunction "P$2_P$2") (pintype "passive"))
      (node (ref "R28") (pin "P$2") (pinfunction "P$2_P$2") (pintype "passive"))
      (node (ref "R8") (pin "P$2") (pinfunction "P$2_P$2") (pintype "passive"))
      (node (ref "U$15") (pin "4") (pinfunction "P4_4") (pintype "bidirectional"))
    )
    (net (code "48") (name "Net-(U$16-P1)") (class "Default")
      (node (ref "C6") (pin "P$2") (pinfunction "P$2_P$2") (pintype "passive"))
      (node (ref "JP3") (pin "3") (pinfunction "3_3") (pintype "passive"))
      (node (ref "R29") (pin "P$1") (pinfunction "P$1_P$1") (pintype "passive"))
      (node (ref "TP5") (pin "TP") (pinfunction "TP_TP") (pintype "input"))
      (node (ref "U$16") (pin "1") (pinfunction "P1_1") (pintype "bidirectional"))
    )
    (net (code "49") (name "Net-(U$16-P4)") (class "Default")
      (node (ref "C6") (pin "P$1") (pinfunction "P$1_P$1") (pintype "passive"))
      (node (ref "R27") (pin "P$2") (pinfunction "P$2_P$2") (pintype "passive"))
      (node (ref "R29") (pin "P$2") (pinfunction "P$2_P$2") (pintype "passive"))
      (node (ref "R34") (pin "P$2") (pinfunction "P$2_P$2") (pintype "passive"))
      (node (ref "U$16") (pin "4") (pinfunction "P4_4") (pintype "bidirectional"))
    )
    (net (code "50") (name "Net-(U$17-P1)") (class "Default")
      (node (ref "C7") (pin "P$2") (pinfunction "P$2_P$2") (pintype "passive"))
      (node (ref "JP3") (pin "4") (pinfunction "4_4") (pintype "passive"))
      (node (ref "R37") (pin "P$1") (pinfunction "P$1_P$1") (pintype "passive"))
      (node (ref "TP6") (pin "TP") (pinfunction "TP_TP") (pintype "input"))
      (node (ref "U$17") (pin "1") (pinfunction "P1_1") (pintype "bidirectional"))
    )
    (net (code "51") (name "Net-(U$17-P4)") (class "Default")
      (node (ref "C7") (pin "P$1") (pinfunction "P$1_P$1") (pintype "passive"))
      (node (ref "R36") (pin "P$2") (pinfunction "P$2_P$2") (pintype "passive"))
      (node (ref "R37") (pin "P$2") (pinfunction "P$2_P$2") (pintype "passive"))
      (node (ref "R41") (pin "P$2") (pinfunction "P$2_P$2") (pintype "passive"))
      (node (ref "U$17") (pin "4") (pinfunction "P4_4") (pintype "bidirectional"))
    )
    (net (code "52") (name "Net-(U1-GATE)") (class "Default")
      (node (ref "R16") (pin "P$2") (pinfunction "P$2_P$2") (pintype "passive"))
      (node (ref "U1") (pin "P$1") (pinfunction "GATE_P$1") (pintype "bidirectional"))
    )
    (net (code "53") (name "Net-(U2-EN)") (class "Default")
      (node (ref "C1") (pin "1") (pinfunction "1_1") (pintype "passive"))
      (node (ref "D1") (pin "CATHODE") (pinfunction "CATHODE_CATHODE") (pintype "bidirectional"))
      (node (ref "R35") (pin "P$2") (pinfunction "P$2_P$2") (pintype "passive"))
      (node (ref "U2") (pin "P$1") (pinfunction "VIN_P$1") (pintype "bidirectional"))
      (node (ref "U2") (pin "P$3") (pinfunction "EN_P$3") (pintype "bidirectional"))
    )
    (net (code "54") (name "Net-(U3-DRAIN)") (class "Default")
      (node (ref "R25") (pin "P$1") (pinfunction "P$1_P$1") (pintype "passive"))
      (node (ref "R42") (pin "P$2") (pinfunction "P$2_P$2") (pintype "passive"))
      (node (ref "U3") (pin "P$3") (pinfunction "DRAIN_P$3") (pintype "bidirectional"))
    )
    (net (code "55") (name "Net-(U3-GATE)") (class "Default")
      (node (ref "C16") (pin "P$1") (pinfunction "P$1_P$1") (pintype "passive"))
      (node (ref "R43") (pin "P$1") (pinfunction "P$1_P$1") (pintype "passive"))
      (node (ref "U3") (pin "P$1") (pinfunction "GATE_P$1") (pintype "bidirectional"))
    )
    (net (code "56") (name "SCK") (class "Default")
      (node (ref "JP5") (pin "3") (pinfunction "3_3") (pintype "passive"))
      (node (ref "U$1") (pin "P15") (pinfunction "PA5_P15") (pintype "bidirectional"))
    )
    (net (code "57") (name "SCL") (class "Default")
      (node (ref "JP6") (pin "4") (pinfunction "4_4") (pintype "passive"))
      (node (ref "U$1") (pin "P6") (pinfunction "PF1_P6") (pintype "bidirectional"))
    )
    (net (code "58") (name "SDA") (class "Default")
      (node (ref "JP6") (pin "2") (pinfunction "2_2") (pintype "passive"))
      (node (ref "U$1") (pin "P5") (pinfunction "PF0_P5") (pintype "bidirectional"))
    )
    (net (code "59") (name "SPI_CS") (class "Default")
      (node (ref "JP5") (pin "5") (pinfunction "5_5") (pintype "passive"))
      (node (ref "U$1") (pin "P18") (pinfunction "PB0_P18") (pintype "bidirectional"))
    )
    (net (code "60") (name "SWCLK") (class "Default")
      (node (ref "SWCLK") (pin "TP") (pinfunction "TP_TP") (pintype "input"))
      (node (ref "U$1") (pin "P37") (pinfunction "PA14_P37") (pintype "bidirectional"))
    )
    (net (code "61") (name "SWDIO") (class "Default")
      (node (ref "SWDIO") (pin "TP") (pinfunction "TP_TP") (pintype "input"))
      (node (ref "U$1") (pin "P34") (pinfunction "PA13_P34") (pintype "bidirectional"))
    )
    (net (code "62") (name "USB_DM") (class "Default")
      (node (ref "J1") (pin "2") (pinfunction "D-_2") (pintype "bidirectional"))
      (node (ref "U$1") (pin "P32") (pinfunction "PA11_P32") (pintype "bidirectional"))
      (node (ref "U$12") (pin "P1") (pinfunction "IO1_P1") (pintype "bidirectional"))
    )
    (net (code "63") (name "USB_DP") (class "Default")
      (node (ref "J1") (pin "3") (pinfunction "D+_3") (pintype "bidirectional"))
      (node (ref "U$1") (pin "P33") (pinfunction "PA12_P33") (pintype "bidirectional"))
      (node (ref "U$12") (pin "P3") (pinfunction "IO2_P3") (pintype "bidirectional"))
    )
    (net (code "64") (name "VUSB") (class "Default")
      (node (ref "C17") (pin "P$1") (pinfunction "P$1_P$1") (pintype "passive"))
      (node (ref "C18") (pin "P$1") (pinfunction "P$1_P$1") (pintype "passive"))
      (node (ref "C19") (pin "P$1") (pinfunction "P$1_P$1") (pintype "passive"))
      (node (ref "C20") (pin "P$1") (pinfunction "P$1_P$1") (pintype "passive"))
      (node (ref "C9") (pin "P$1") (pinfunction "P$1_P$1") (pintype "passive"))
      (node (ref "D1") (pin "ANODE") (pinfunction "ANODE_ANODE") (pintype "bidirectional"))
      (node (ref "L1") (pin "1") (pinfunction "1_1") (pintype "passive"))
      (node (ref "R19") (pin "P$1") (pinfunction "P$1_P$1") (pintype "passive"))
      (node (ref "U$10") (pin "CATHODE") (pinfunction "CATHODE_CATHODE") (pintype "bidirectional"))
      (node (ref "U$12") (pin "P5") (pinfunction "VCC_P5") (pintype "power_in"))
      (node (ref "U$13") (pin "CATHODE") (pinfunction "CATHODE_CATHODE") (pintype "bidirectional"))
      (node (ref "U$14") (pin "P$1") (pinfunction "P$1_P$1") (pintype "bidirectional"))
      (node (ref "U$15") (pin "2") (pinfunction "P2_2") (pintype "power_in"))
      (node (ref "U$16") (pin "2") (pinfunction "P2_2") (pintype "power_in"))
      (node (ref "U$17") (pin "2") (pinfunction "P2_2") (pintype "power_in"))
      (node (ref "U$7") (pin "2") (pinfunction "P2_2") (pintype "power_in"))
      (node (ref "U$8") (pin "5") (pinfunction "VIN_5") (pintype "bidirectional"))
      (node (ref "VUSB") (pin "TP") (pinfunction "TP_TP") (pintype "input"))
    )
    (net (code "65") (name "XCOARSE_IN") (class "Default")
      (node (ref "R5") (pin "P$1") (pinfunction "P$1_P$1") (pintype "passive"))
      (node (ref "U$1") (pin "P38") (pinfunction "PA15_P38") (pintype "bidirectional"))
      (node (ref "U$2") (pin "P1") (pinfunction "A1_P1") (pintype "input"))
    )
    (net (code "66") (name "XFINE_IN") (class "Default")
      (node (ref "R31") (pin "P$1") (pinfunction "P$1_P$1") (pintype "passive"))
      (node (ref "R6") (pin "P$1") (pinfunction "P$1_P$1") (pintype "passive"))
      (node (ref "U$1") (pin "P39") (pinfunction "PB3_P39") (pintype "bidirectional"))
      (node (ref "U$2") (pin "P3") (pinfunction "A2_P3") (pintype "input"))
    )
    (net (code "67") (name "YCOARSE_IN") (class "Default")
      (node (ref "R27") (pin "P$1") (pinfunction "P$1_P$1") (pintype "passive"))
      (node (ref "U$1") (pin "P21") (pinfunction "PB10_P21") (pintype "bidirectional"))
      (node (ref "U$4") (pin "P1") (pinfunction "A1_P1") (pintype "input"))
    )
    (net (code "68") (name "YFINE_IN") (class "Default")
      (node (ref "R30") (pin "P$1") (pinfunction "P$1_P$1") (pintype "passive"))
      (node (ref "R33") (pin "P$1") (pinfunction "P$1_P$1") (pintype "passive"))
      (node (ref "U$1") (pin "P22") (pinfunction "PB11_P22") (pintype "bidirectional"))
      (node (ref "U$4") (pin "P3") (pinfunction "A2_P3") (pintype "input"))
    )
    (net (code "69") (name "unconnected-(U$1-PA4-PadP14)") (class "Default")
      (node (ref "U$1") (pin "P14") (pinfunction "PA4_P14") (pintype "bidirectional"))
    )
    (net (code "70") (name "unconnected-(U$1-PA8-PadP29)") (class "Default")
      (node (ref "U$1") (pin "P29") (pinfunction "PA8_P29") (pintype "bidirectional"))
    )
    (net (code "71") (name "unconnected-(U$1-PA9-PadP30)") (class "Default")
      (node (ref "U$1") (pin "P30") (pinfunction "PA9_P30") (pintype "bidirectional"))
    )
    (net (code "72") (name "unconnected-(U$1-PA10-PadP31)") (class "Default")
      (node (ref "U$1") (pin "P31") (pinfunction "PA10_P31") (pintype "bidirectional"))
    )
    (net (code "73") (name "unconnected-(U$1-PB1-PadP19)") (class "Default")
      (node (ref "U$1") (pin "P19") (pinfunction "PB1_P19") (pintype "bidirectional"))
    )
    (net (code "74") (name "unconnected-(U$1-PB2-PadP20)") (class "Default")
      (node (ref "U$1") (pin "P20") (pinfunction "PB2_P20") (pintype "bidirectional"))
    )
    (net (code "75") (name "unconnected-(U$1-PB6-PadP42)") (class "Default")
      (node (ref "U$1") (pin "P42") (pinfunction "PB6_P42") (pintype "bidirectional"))
    )
    (net (code "76") (name "unconnected-(U$1-PB7-PadP43)") (class "Default")
      (node (ref "U$1") (pin "P43") (pinfunction "PB7_P43") (pintype "bidirectional"))
    )
    (net (code "77") (name "unconnected-(U$1-PB8-PadP45)") (class "Default")
      (node (ref "U$1") (pin "P45") (pinfunction "PB8_P45") (pintype "bidirectional"))
    )
    (net (code "78") (name "unconnected-(U$1-PB9-PadP46)") (class "Default")
      (node (ref "U$1") (pin "P46") (pinfunction "PB9_P46") (pintype "bidirectional"))
    )
    (net (code "79") (name "unconnected-(U$1-PC13-PadP2)") (class "Default")
      (node (ref "U$1") (pin "P2") (pinfunction "PC13_P2") (pintype "bidirectional"))
    )
    (net (code "80") (name "unconnected-(U$1-PC14-PadP3)") (class "Default")
      (node (ref "U$1") (pin "P3") (pinfunction "PC14_P3") (pintype "bidirectional"))
    )
    (net (code "81") (name "unconnected-(U$1-PC15-PadP4)") (class "Default")
      (node (ref "U$1") (pin "P4") (pinfunction "PC15_P4") (pintype "bidirectional"))
    )
    (net (code "82") (name "unconnected-(U$12-IO3-PadP4)") (class "Default")
      (node (ref "U$12") (pin "P4") (pinfunction "IO3_P4") (pintype "bidirectional"))
    )
    (net (code "83") (name "unconnected-(U$12-IO4-PadP6)") (class "Default")
      (node (ref "U$12") (pin "P6") (pinfunction "IO4_P6") (pintype "bidirectional"))
    )
  )
)
